# TLC5940Shield-v1.net
KiCad netlist of a schematic drawn in EAGLE
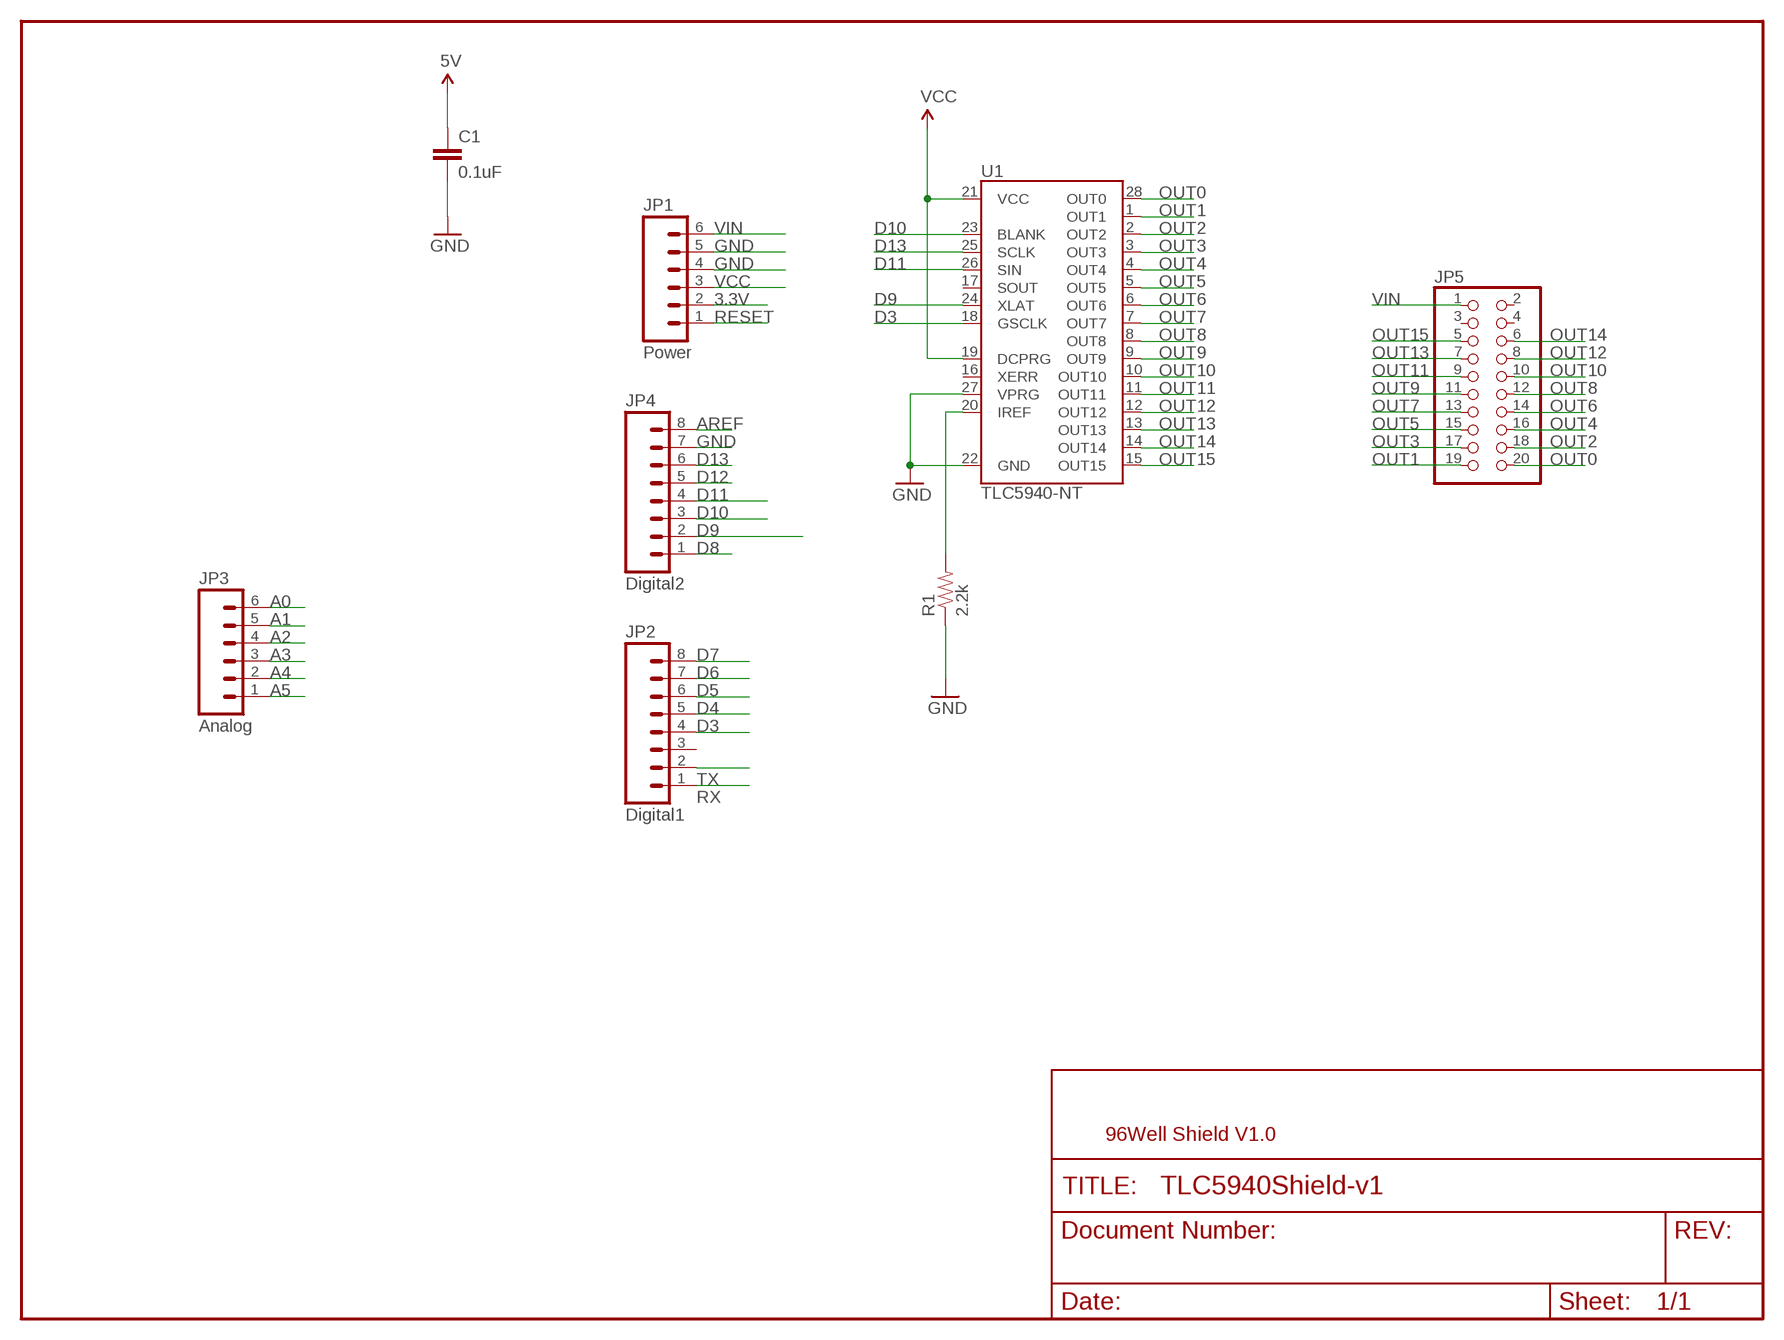
[diagram p0: schematic, sheet 1]

(export (version "E")
  (design (tool "Eeschema 10.0.6"))
  (components
    (comp (ref "C1")
      (value "0.1uF")
      (footprint "eagle-import:0402-CAP")
      (libsource (lib "eagle-import") (part "CAP0402-CAP"))
    )
    (comp (ref "JP1")
      (value "Power")
      (footprint "eagle-import:1X06")
      (libsource (lib "eagle-import") (part "M06SIP"))
    )
    (comp (ref "JP2")
      (value "Digital1")
      (footprint "eagle-import:1X08")
      (libsource (lib "eagle-import") (part "M08"))
    )
    (comp (ref "JP3")
      (value "Analog")
      (footprint "eagle-import:1X06")
      (libsource (lib "eagle-import") (part "M06SIP"))
    )
    (comp (ref "JP4")
      (value "Digital2")
      (footprint "eagle-import:1X08")
      (libsource (lib "eagle-import") (part "M08"))
    )
    (comp (ref "JP5")
      (value "PINHD-2X10")
      (footprint "eagle-import:2X10")
      (libsource (lib "eagle-import") (part "PINHD-2X10"))
    )
    (comp (ref "R1")
      (value "2.2k")
      (footprint "eagle-import:AXIAL-0.4")
      (libsource (lib "eagle-import") (part "RESISTORPTH-1/4W"))
    )
    (comp (ref "U1")
      (value "TLC5940-NT")
      (footprint "eagle-import:DIL28-3")
      (libsource (lib "eagle-import") (part "TLC5940-NT"))
    )
  )
  (nets
    (net (code "1") (name "/3.3V") (class "Default")
      (node (ref "JP1") (pin "2") (pinfunction "2_2") (pintype "passive"))
    )
    (net (code "2") (name "/A0") (class "Default")
      (node (ref "JP3") (pin "6") (pinfunction "6_6") (pintype "passive"))
    )
    (net (code "3") (name "/A1") (class "Default")
      (node (ref "JP3") (pin "5") (pinfunction "5_5") (pintype "passive"))
    )
    (net (code "4") (name "/A2") (class "Default")
      (node (ref "JP3") (pin "4") (pinfunction "4_4") (pintype "passive"))
    )
    (net (code "5") (name "/A3") (class "Default")
      (node (ref "JP3") (pin "3") (pinfunction "3_3") (pintype "passive"))
    )
    (net (code "6") (name "/A4") (class "Default")
      (node (ref "JP3") (pin "2") (pinfunction "2_2") (pintype "passive"))
    )
    (net (code "7") (name "/A5") (class "Default")
      (node (ref "JP3") (pin "1") (pinfunction "1_1") (pintype "passive"))
    )
    (net (code "8") (name "/AREF") (class "Default")
      (node (ref "JP4") (pin "8") (pinfunction "8_8") (pintype "passive"))
    )
    (net (code "9") (name "/D3") (class "Default")
      (node (ref "JP2") (pin "4") (pinfunction "4_4") (pintype "passive"))
      (node (ref "U1") (pin "18") (pinfunction "GSCLK_18") (pintype "bidirectional"))
    )
    (net (code "10") (name "/D4") (class "Default")
      (node (ref "JP2") (pin "5") (pinfunction "5_5") (pintype "passive"))
    )
    (net (code "11") (name "/D5") (class "Default")
      (node (ref "JP2") (pin "6") (pinfunction "6_6") (pintype "passive"))
    )
    (net (code "12") (name "/D6") (class "Default")
      (node (ref "JP2") (pin "7") (pinfunction "7_7") (pintype "passive"))
    )
    (net (code "13") (name "/D7") (class "Default")
      (node (ref "JP2") (pin "8") (pinfunction "8_8") (pintype "passive"))
    )
    (net (code "14") (name "/D8") (class "Default")
      (node (ref "JP4") (pin "1") (pinfunction "1_1") (pintype "passive"))
    )
    (net (code "15") (name "/D9") (class "Default")
      (node (ref "JP4") (pin "2") (pinfunction "2_2") (pintype "passive"))
      (node (ref "U1") (pin "24") (pinfunction "XLAT_24") (pintype "bidirectional"))
    )
    (net (code "16") (name "/D10") (class "Default")
      (node (ref "JP4") (pin "3") (pinfunction "3_3") (pintype "passive"))
      (node (ref "U1") (pin "23") (pinfunction "BLANK_23") (pintype "bidirectional"))
    )
    (net (code "17") (name "/D11") (class "Default")
      (node (ref "JP4") (pin "4") (pinfunction "4_4") (pintype "passive"))
      (node (ref "U1") (pin "26") (pinfunction "SIN_26") (pintype "bidirectional"))
    )
    (net (code "18") (name "/D12") (class "Default")
      (node (ref "JP4") (pin "5") (pinfunction "5_5") (pintype "passive"))
    )
    (net (code "19") (name "/D13") (class "Default")
      (node (ref "JP4") (pin "6") (pinfunction "6_6") (pintype "passive"))
      (node (ref "U1") (pin "25") (pinfunction "SCLK_25") (pintype "bidirectional"))
    )
    (net (code "20") (name "/OUT0") (class "Default")
      (node (ref "JP5") (pin "20") (pinfunction "20_20") (pintype "passive"))
      (node (ref "U1") (pin "28") (pinfunction "OUT0_28") (pintype "bidirectional"))
    )
    (net (code "21") (name "/OUT1") (class "Default")
      (node (ref "JP5") (pin "19") (pinfunction "19_19") (pintype "passive"))
      (node (ref "U1") (pin "1") (pinfunction "OUT1_1") (pintype "bidirectional"))
    )
    (net (code "22") (name "/OUT2") (class "Default")
      (node (ref "JP5") (pin "18") (pinfunction "18_18") (pintype "passive"))
      (node (ref "U1") (pin "2") (pinfunction "OUT2_2") (pintype "bidirectional"))
    )
    (net (code "23") (name "/OUT3") (class "Default")
      (node (ref "JP5") (pin "17") (pinfunction "17_17") (pintype "passive"))
      (node (ref "U1") (pin "3") (pinfunction "OUT3_3") (pintype "bidirectional"))
    )
    (net (code "24") (name "/OUT4") (class "Default")
      (node (ref "JP5") (pin "16") (pinfunction "16_16") (pintype "passive"))
      (node (ref "U1") (pin "4") (pinfunction "OUT4_4") (pintype "bidirectional"))
    )
    (net (code "25") (name "/OUT5") (class "Default")
      (node (ref "JP5") (pin "15") (pinfunction "15_15") (pintype "passive"))
      (node (ref "U1") (pin "5") (pinfunction "OUT5_5") (pintype "bidirectional"))
    )
    (net (code "26") (name "/OUT6") (class "Default")
      (node (ref "JP5") (pin "14") (pinfunction "14_14") (pintype "passive"))
      (node (ref "U1") (pin "6") (pinfunction "OUT6_6") (pintype "bidirectional"))
    )
    (net (code "27") (name "/OUT7") (class "Default")
      (node (ref "JP5") (pin "13") (pinfunction "13_13") (pintype "passive"))
      (node (ref "U1") (pin "7") (pinfunction "OUT7_7") (pintype "bidirectional"))
    )
    (net (code "28") (name "/OUT8") (class "Default")
      (node (ref "JP5") (pin "12") (pinfunction "12_12") (pintype "passive"))
      (node (ref "U1") (pin "8") (pinfunction "OUT8_8") (pintype "bidirectional"))
    )
    (net (code "29") (name "/OUT9") (class "Default")
      (node (ref "JP5") (pin "11") (pinfunction "11_11") (pintype "passive"))
      (node (ref "U1") (pin "9") (pinfunction "OUT9_9") (pintype "bidirectional"))
    )
    (net (code "30") (name "/OUT10") (class "Default")
      (node (ref "JP5") (pin "10") (pinfunction "10_10") (pintype "passive"))
      (node (ref "U1") (pin "10") (pinfunction "OUT10_10") (pintype "bidirectional"))
    )
    (net (code "31") (name "/OUT11") (class "Default")
      (node (ref "JP5") (pin "9") (pinfunction "9_9") (pintype "passive"))
      (node (ref "U1") (pin "11") (pinfunction "OUT11_11") (pintype "bidirectional"))
    )
    (net (code "32") (name "/OUT12") (class "Default")
      (node (ref "JP5") (pin "8") (pinfunction "8_8") (pintype "passive"))
      (node (ref "U1") (pin "12") (pinfunction "OUT12_12") (pintype "bidirectional"))
    )
    (net (code "33") (name "/OUT13") (class "Default")
      (node (ref "JP5") (pin "7") (pinfunction "7_7") (pintype "passive"))
      (node (ref "U1") (pin "13") (pinfunction "OUT13_13") (pintype "bidirectional"))
    )
    (net (code "34") (name "/OUT14") (class "Default")
      (node (ref "JP5") (pin "6") (pinfunction "6_6") (pintype "passive"))
      (node (ref "U1") (pin "14") (pinfunction "OUT14_14") (pintype "bidirectional"))
    )
    (net (code "35") (name "/OUT15") (class "Default")
      (node (ref "JP5") (pin "5") (pinfunction "5_5") (pintype "passive"))
      (node (ref "U1") (pin "15") (pinfunction "OUT15_15") (pintype "bidirectional"))
    )
    (net (code "36") (name "/RESET") (class "Default")
      (node (ref "JP1") (pin "1") (pinfunction "1_1") (pintype "passive"))
    )
    (net (code "37") (name "/RX") (class "Default")
      (node (ref "JP2") (pin "1") (pinfunction "1_1") (pintype "passive"))
    )
    (net (code "38") (name "/TX") (class "Default")
      (node (ref "JP2") (pin "2") (pinfunction "2_2") (pintype "passive"))
    )
    (net (code "39") (name "/VIN") (class "Default")
      (node (ref "JP1") (pin "6") (pinfunction "6_6") (pintype "passive"))
      (node (ref "JP5") (pin "1") (pinfunction "1_1") (pintype "passive"))
    )
    (net (code "40") (name "5V") (class "Default")
      (node (ref "C1") (pin "1") (pinfunction "1_1") (pintype "passive"))
      (node (ref "JP1") (pin "3") (pinfunction "3_3") (pintype "passive"))
      (node (ref "U1") (pin "19") (pinfunction "DCPRG_19") (pintype "bidirectional"))
      (node (ref "U1") (pin "21") (pinfunction "VCC_21") (pintype "bidirectional"))
    )
    (net (code "41") (name "GND") (class "Default")
      (node (ref "C1") (pin "2") (pinfunction "2_2") (pintype "passive"))
      (node (ref "JP1") (pin "4") (pinfunction "4_4") (pintype "passive"))
      (node (ref "JP1") (pin "5") (pinfunction "5_5") (pintype "passive"))
      (node (ref "JP4") (pin "7") (pinfunction "7_7") (pintype "passive"))
      (node (ref "R1") (pin "P$1") (pinfunction "1_P$1") (pintype "passive"))
      (node (ref "U1") (pin "22") (pinfunction "GND_22") (pintype "bidirectional"))
      (node (ref "U1") (pin "27") (pinfunction "VPRG_27") (pintype "bidirectional"))
    )
    (net (code "42") (name "Net-(R1-2)") (class "Default")
      (node (ref "R1") (pin "P$2") (pinfunction "2_P$2") (pintype "passive"))
      (node (ref "U1") (pin "20") (pinfunction "IREF_20") (pintype "bidirectional"))
    )
    (net (code "43") (name "unconnected-(JP2-Pad3)") (class "Default")
      (node (ref "JP2") (pin "3") (pinfunction "3_3") (pintype "passive"))
    )
    (net (code "44") (name "unconnected-(JP5-Pad2)") (class "Default")
      (node (ref "JP5") (pin "2") (pinfunction "2_2") (pintype "passive"))
    )
    (net (code "45") (name "unconnected-(JP5-Pad3)") (class "Default")
      (node (ref "JP5") (pin "3") (pinfunction "3_3") (pintype "passive"))
    )
    (net (code "46") (name "unconnected-(JP5-Pad4)") (class "Default")
      (node (ref "JP5") (pin "4") (pinfunction "4_4") (pintype "passive"))
    )
    (net (code "47") (name "unconnected-(U1-SOUT-Pad17)") (class "Default")
      (node (ref "U1") (pin "17") (pinfunction "SOUT_17") (pintype "bidirectional"))
    )
    (net (code "48") (name "unconnected-(U1-XERR-Pad16)") (class "Default")
      (node (ref "U1") (pin "16") (pinfunction "XERR_16") (pintype "bidirectional"))
    )
  )
)
